# 32u4_Simple_Breakout.net
KiCad netlist of a schematic drawn in EAGLE
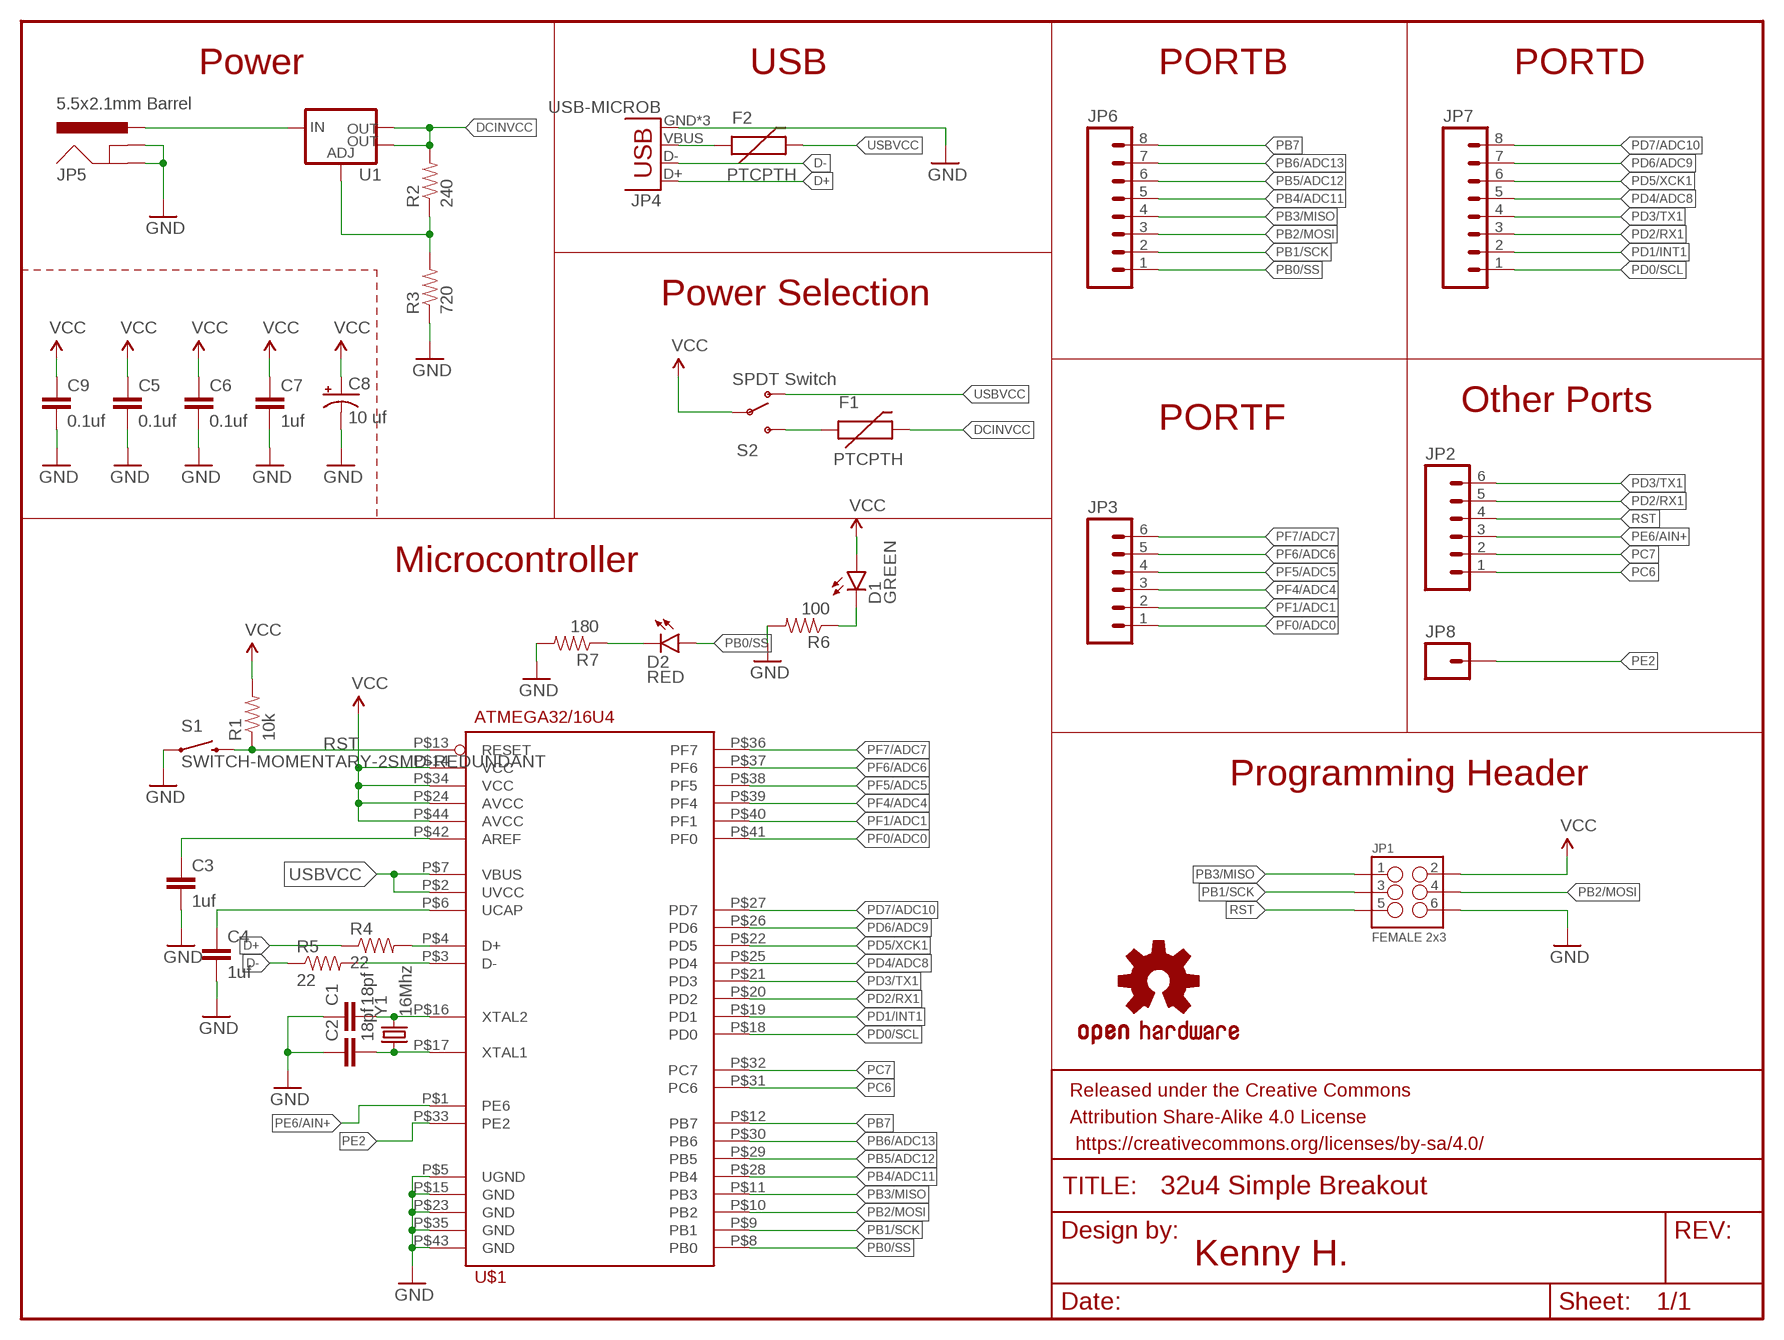
[diagram p0: schematic, sheet 1]

(export (version "E")
  (design (tool "Eeschema 10.0.6"))
  (components
    (comp (ref "C1")
      (value "18pf")
      (footprint "eagle-import:0603-CAP")
      (libsource (lib "eagle-import") (part "CAP0603-CAP"))
    )
    (comp (ref "C2")
      (value "18pf")
      (footprint "eagle-import:0603-CAP")
      (libsource (lib "eagle-import") (part "CAP0603-CAP"))
    )
    (comp (ref "C3")
      (value "1uf")
      (footprint "eagle-import:0603-CAP")
      (libsource (lib "eagle-import") (part "CAP0603-CAP"))
    )
    (comp (ref "C4")
      (value "1uf")
      (footprint "eagle-import:0603-CAP")
      (libsource (lib "eagle-import") (part "CAP0603-CAP"))
    )
    (comp (ref "C5")
      (value "0.1uf")
      (footprint "eagle-import:0603-CAP")
      (libsource (lib "eagle-import") (part "CAP0603-CAP"))
    )
    (comp (ref "C6")
      (value "0.1uf")
      (footprint "eagle-import:0603-CAP")
      (libsource (lib "eagle-import") (part "CAP0603-CAP"))
    )
    (comp (ref "C7")
      (value "1uf")
      (footprint "eagle-import:0603-CAP")
      (libsource (lib "eagle-import") (part "CAP0603-CAP"))
    )
    (comp (ref "C8")
      (value "10 uf")
      (footprint "eagle-import:CPOL-RADIAL-10UF-25V")
      (libsource (lib "eagle-import") (part "CAP_POLPTH2"))
    )
    (comp (ref "C9")
      (value "0.1uf")
      (footprint "eagle-import:0603-CAP")
      (libsource (lib "eagle-import") (part "CAP0603-CAP"))
    )
    (comp (ref "D1")
      (value "GREEN")
      (footprint "eagle-import:LED-1206")
      (libsource (lib "eagle-import") (part "LED-GREEN1206"))
    )
    (comp (ref "D2")
      (value "RED")
      (footprint "eagle-import:LED-1206")
      (libsource (lib "eagle-import") (part "LED-RED1206"))
    )
    (comp (ref "F1")
      (value "PTCPTH")
      (footprint "eagle-import:PTC")
      (libsource (lib "eagle-import") (part "PTCPTH"))
    )
    (comp (ref "F2")
      (value "PTCPTH")
      (footprint "eagle-import:PTC")
      (libsource (lib "eagle-import") (part "PTCPTH"))
    )
    (comp (ref "FRAME1")
      (value "FRAME-LETTER")
      (footprint "eagle-import:CREATIVE_COMMONS")
      (libsource (lib "eagle-import") (part "FRAME-LETTER"))
    )
    (comp (ref "JP1")
      (value "FEMALE 2x3")
      (footprint "eagle-import:2X3")
      (libsource (lib "eagle-import") (part "M03X2FEMALE"))
    )
    (comp (ref "JP2")
      (value "M06FEMALE_LOCK")
      (footprint "eagle-import:1X06_FEMALE_LOCK.010")
      (libsource (lib "eagle-import") (part "M06FEMALE_LOCK"))
    )
    (comp (ref "JP3")
      (value "M06FEMALE_LOCK")
      (footprint "eagle-import:1X06_FEMALE_LOCK.010")
      (libsource (lib "eagle-import") (part "M06FEMALE_LOCK"))
    )
    (comp (ref "JP4")
      (value "USB-MICROB")
      (footprint "eagle-import:USB-MICROB")
      (libsource (lib "eagle-import") (part "USB-MICROB"))
    )
    (comp (ref "JP5")
      (value "5.5x2.1mm Barrel")
      (footprint "eagle-import:POWER_JACK_SMD")
      (libsource (lib "eagle-import") (part "POWER_JACKSMD"))
    )
    (comp (ref "JP6")
      (value "M08FEMALE_LOCK")
      (footprint "eagle-import:1X08_FEMALE_LOCK")
      (libsource (lib "eagle-import") (part "M08FEMALE_LOCK"))
    )
    (comp (ref "JP7")
      (value "M08FEMALE_LOCK")
      (footprint "eagle-import:1X08_FEMALE_LOCK")
      (libsource (lib "eagle-import") (part "M08FEMALE_LOCK"))
    )
    (comp (ref "JP8")
      (value "M01PTH")
      (footprint "eagle-import:1X01")
      (libsource (lib "eagle-import") (part "M01PTH"))
    )
    (comp (ref "LOGO1")
      (value "OSHW-LOGOM")
      (footprint "eagle-import:OSHW-LOGO-M")
      (libsource (lib "eagle-import") (part "OSHW-LOGOM"))
    )
    (comp (ref "R1")
      (value "10k")
      (footprint "eagle-import:0603-RES")
      (libsource (lib "eagle-import") (part "RESISTOR0603-RES"))
    )
    (comp (ref "R2")
      (value "240")
      (footprint "eagle-import:0603-RES")
      (libsource (lib "eagle-import") (part "RESISTOR0603-RES"))
    )
    (comp (ref "R3")
      (value "720")
      (footprint "eagle-import:0603-RES")
      (libsource (lib "eagle-import") (part "RESISTOR0603-RES"))
    )
    (comp (ref "R4")
      (value "22")
      (footprint "eagle-import:0603-RES")
      (libsource (lib "eagle-import") (part "SparkFun-Resistors_RESISTOR0603-RES"))
    )
    (comp (ref "R5")
      (value "22")
      (footprint "eagle-import:0603-RES")
      (libsource (lib "eagle-import") (part "SparkFun-Resistors_RESISTOR0603-RES"))
    )
    (comp (ref "R6")
      (value "100")
      (footprint "eagle-import:1206")
      (libsource (lib "eagle-import") (part "SparkFun-Resistors_RESISTOR1206"))
    )
    (comp (ref "R7")
      (value "180")
      (footprint "eagle-import:1206")
      (libsource (lib "eagle-import") (part "SparkFun-Resistors_RESISTOR1206"))
    )
    (comp (ref "S1")
      (value "SWITCH-MOMENTARY-2SMD-REDUNDANT")
      (footprint "eagle-import:TACTILE-SWITCH-SMD")
      (libsource (lib "eagle-import") (part "SWITCH-MOMENTARY-2SMD-REDUNDANT"))
    )
    (comp (ref "S2")
      (value "SPDT Switch")
      (footprint "eagle-import:SWITCH-SPST-SMD-A")
      (libsource (lib "eagle-import") (part "SWITCH-SPDT-SMD-A"))
    )
    (comp (ref "U$1")
      (value "ATMEGA32/16U4")
      (footprint "eagle-import:TQFP_44_0.8MM")
      (libsource (lib "eagle-import") (part "ATMEGA32/16U4"))
    )
    (comp (ref "U1")
      (value "V_REG_LM1117SOT223")
      (footprint "eagle-import:SOT223")
      (libsource (lib "eagle-import") (part "V_REG_LM1117SOT223"))
    )
    (comp (ref "Y1")
      (value "16Mhz")
      (footprint "eagle-import:CRYSTAL-SMD-5X3")
      (libsource (lib "eagle-import") (part "CRYSTAL5X3"))
    )
  )
  (nets
    (net (code "1") (name "D+") (class "Default")
      (node (ref "JP4") (pin "D+") (pinfunction "D+_D+") (pintype "bidirectional"))
      (node (ref "R4") (pin "1") (pinfunction "1_1") (pintype "passive"))
    )
    (net (code "2") (name "D-") (class "Default")
      (node (ref "JP4") (pin "D-") (pinfunction "D-_D-") (pintype "bidirectional"))
      (node (ref "R5") (pin "1") (pinfunction "1_1") (pintype "passive"))
    )
    (net (code "3") (name "DCINVCC") (class "Default")
      (node (ref "F1") (pin "P$2") (pinfunction "2_P$2") (pintype "bidirectional"))
      (node (ref "R2") (pin "2") (pinfunction "2_2") (pintype "passive"))
      (node (ref "U1") (pin "2") (pinfunction "OUT_2") (pintype "output"))
      (node (ref "U1") (pin "4") (pinfunction "OUT_4") (pintype "output"))
    )
    (net (code "4") (name "GND") (class "Default")
      (node (ref "C1") (pin "1") (pinfunction "1_1") (pintype "passive"))
      (node (ref "C2") (pin "1") (pinfunction "1_1") (pintype "passive"))
      (node (ref "C3") (pin "2") (pinfunction "2_2") (pintype "passive"))
      (node (ref "C4") (pin "2") (pinfunction "2_2") (pintype "passive"))
      (node (ref "C5") (pin "2") (pinfunction "2_2") (pintype "passive"))
      (node (ref "C6") (pin "2") (pinfunction "2_2") (pintype "passive"))
      (node (ref "C7") (pin "2") (pinfunction "2_2") (pintype "passive"))
      (node (ref "C8") (pin "2") (pinfunction "-_2") (pintype "passive"))
      (node (ref "C9") (pin "2") (pinfunction "2_2") (pintype "passive"))
      (node (ref "JP1") (pin "6") (pinfunction "6_6") (pintype "bidirectional"))
      (node (ref "JP4") (pin "GND") (pinfunction "GND_GND") (pintype "bidirectional"))
      (node (ref "JP4") (pin "MT1") (pinfunction "GND_MT1") (pintype "bidirectional"))
      (node (ref "JP4") (pin "MT2") (pinfunction "GND_MT2") (pintype "bidirectional"))
      (node (ref "JP5") (pin "GND") (pinfunction "GNDBREAK_GND") (pintype "bidirectional"))
      (node (ref "JP5") (pin "P$4") (pinfunction "GND_P$4") (pintype "bidirectional"))
      (node (ref "R3") (pin "1") (pinfunction "1_1") (pintype "passive"))
      (node (ref "R6") (pin "2") (pinfunction "2_2") (pintype "passive"))
      (node (ref "R7") (pin "2") (pinfunction "2_2") (pintype "passive"))
      (node (ref "S1") (pin "1") (pinfunction "1_1") (pintype "passive"))
      (node (ref "S1") (pin "2") (pinfunction "1_2") (pintype "passive"))
      (node (ref "U$1") (pin "P$15") (pinfunction "GND_P$15") (pintype "power_in"))
      (node (ref "U$1") (pin "P$23") (pinfunction "GND_P$23") (pintype "power_in"))
      (node (ref "U$1") (pin "P$35") (pinfunction "GND_P$35") (pintype "power_in"))
      (node (ref "U$1") (pin "P$43") (pinfunction "GND_P$43") (pintype "power_in"))
      (node (ref "U$1") (pin "P$5") (pinfunction "UGND_P$5") (pintype "power_in"))
    )
    (net (code "5") (name "Net-(D1-PadC)") (class "Default")
      (node (ref "D1") (pin "C") (pinfunction "C_C") (pintype "passive"))
      (node (ref "R6") (pin "1") (pinfunction "1_1") (pintype "passive"))
    )
    (net (code "6") (name "Net-(D2-PadC)") (class "Default")
      (node (ref "D2") (pin "C") (pinfunction "C_C") (pintype "passive"))
      (node (ref "R7") (pin "1") (pinfunction "1_1") (pintype "passive"))
    )
    (net (code "7") (name "Net-(F1-1)") (class "Default")
      (node (ref "F1") (pin "P$1") (pinfunction "1_P$1") (pintype "bidirectional"))
      (node (ref "S2") (pin "3") (pinfunction "S_3") (pintype "passive"))
    )
    (net (code "8") (name "Net-(F2-1)") (class "Default")
      (node (ref "F2") (pin "P$1") (pinfunction "1_P$1") (pintype "bidirectional"))
      (node (ref "JP4") (pin "VBUS") (pinfunction "VBUS_VBUS") (pintype "bidirectional"))
    )
    (net (code "9") (name "Net-(JP5-PWR)") (class "Default")
      (node (ref "JP5") (pin "VIN0") (pinfunction "PWR_VIN0") (pintype "bidirectional"))
      (node (ref "U1") (pin "3") (pinfunction "IN_3") (pintype "input"))
    )
    (net (code "10") (name "Net-(U$1-AREF)") (class "Default")
      (node (ref "C3") (pin "1") (pinfunction "1_1") (pintype "passive"))
      (node (ref "U$1") (pin "P$42") (pinfunction "AREF_P$42") (pintype "power_in"))
    )
    (net (code "11") (name "Net-(U$1-D+)") (class "Default")
      (node (ref "R4") (pin "2") (pinfunction "2_2") (pintype "passive"))
      (node (ref "U$1") (pin "P$4") (pinfunction "D+_P$4") (pintype "bidirectional"))
    )
    (net (code "12") (name "Net-(U$1-D-)") (class "Default")
      (node (ref "R5") (pin "2") (pinfunction "2_2") (pintype "passive"))
      (node (ref "U$1") (pin "P$3") (pinfunction "D-_P$3") (pintype "bidirectional"))
    )
    (net (code "13") (name "Net-(U$1-UCAP)") (class "Default")
      (node (ref "C4") (pin "1") (pinfunction "1_1") (pintype "passive"))
      (node (ref "U$1") (pin "P$6") (pinfunction "UCAP_P$6") (pintype "power_in"))
    )
    (net (code "14") (name "Net-(U$1-XTAL1)") (class "Default")
      (node (ref "C2") (pin "2") (pinfunction "2_2") (pintype "passive"))
      (node (ref "U$1") (pin "P$17") (pinfunction "XTAL1_P$17") (pintype "input"))
      (node (ref "Y1") (pin "1") (pinfunction "1_1") (pintype "passive"))
    )
    (net (code "15") (name "Net-(U$1-XTAL2)") (class "Default")
      (node (ref "C1") (pin "2") (pinfunction "2_2") (pintype "passive"))
      (node (ref "U$1") (pin "P$16") (pinfunction "XTAL2_P$16") (pintype "input"))
      (node (ref "Y1") (pin "3") (pinfunction "2_3") (pintype "passive"))
    )
    (net (code "16") (name "Net-(U1-ADJ)") (class "Default")
      (node (ref "R2") (pin "1") (pinfunction "1_1") (pintype "passive"))
      (node (ref "R3") (pin "2") (pinfunction "2_2") (pintype "passive"))
      (node (ref "U1") (pin "1") (pinfunction "ADJ_1") (pintype "input"))
    )
    (net (code "17") (name "PB0{slash}SS") (class "Default")
      (node (ref "D2") (pin "A") (pinfunction "A_A") (pintype "passive"))
      (node (ref "JP6") (pin "1") (pinfunction "1_1") (pintype "passive"))
      (node (ref "U$1") (pin "P$8") (pinfunction "PB0_P$8") (pintype "bidirectional"))
    )
    (net (code "18") (name "PB1{slash}SCK") (class "Default")
      (node (ref "JP1") (pin "3") (pinfunction "3_3") (pintype "bidirectional"))
      (node (ref "JP6") (pin "2") (pinfunction "2_2") (pintype "passive"))
      (node (ref "U$1") (pin "P$9") (pinfunction "PB1_P$9") (pintype "bidirectional"))
    )
    (net (code "19") (name "PB2{slash}MOSI") (class "Default")
      (node (ref "JP1") (pin "4") (pinfunction "4_4") (pintype "bidirectional"))
      (node (ref "JP6") (pin "3") (pinfunction "3_3") (pintype "passive"))
      (node (ref "U$1") (pin "P$10") (pinfunction "PB2_P$10") (pintype "bidirectional"))
    )
    (net (code "20") (name "PB3{slash}MISO") (class "Default")
      (node (ref "JP1") (pin "1") (pinfunction "1_1") (pintype "bidirectional"))
      (node (ref "JP6") (pin "4") (pinfunction "4_4") (pintype "passive"))
      (node (ref "U$1") (pin "P$11") (pinfunction "PB3_P$11") (pintype "bidirectional"))
    )
    (net (code "21") (name "PB4{slash}ADC11") (class "Default")
      (node (ref "JP6") (pin "5") (pinfunction "5_5") (pintype "passive"))
      (node (ref "U$1") (pin "P$28") (pinfunction "PB4_P$28") (pintype "bidirectional"))
    )
    (net (code "22") (name "PB5{slash}ADC12") (class "Default")
      (node (ref "JP6") (pin "6") (pinfunction "6_6") (pintype "passive"))
      (node (ref "U$1") (pin "P$29") (pinfunction "PB5_P$29") (pintype "bidirectional"))
    )
    (net (code "23") (name "PB6{slash}ADC13") (class "Default")
      (node (ref "JP6") (pin "7") (pinfunction "7_7") (pintype "passive"))
      (node (ref "U$1") (pin "P$30") (pinfunction "PB6_P$30") (pintype "bidirectional"))
    )
    (net (code "24") (name "PB7") (class "Default")
      (node (ref "JP6") (pin "8") (pinfunction "8_8") (pintype "passive"))
      (node (ref "U$1") (pin "P$12") (pinfunction "PB7_P$12") (pintype "bidirectional"))
    )
    (net (code "25") (name "PC6") (class "Default")
      (node (ref "JP2") (pin "1") (pinfunction "1_1") (pintype "passive"))
      (node (ref "U$1") (pin "P$31") (pinfunction "PC6_P$31") (pintype "bidirectional"))
    )
    (net (code "26") (name "PC7") (class "Default")
      (node (ref "JP2") (pin "2") (pinfunction "2_2") (pintype "passive"))
      (node (ref "U$1") (pin "P$32") (pinfunction "PC7_P$32") (pintype "bidirectional"))
    )
    (net (code "27") (name "PD0{slash}SCL") (class "Default")
      (node (ref "JP7") (pin "1") (pinfunction "1_1") (pintype "passive"))
      (node (ref "U$1") (pin "P$18") (pinfunction "PD0_P$18") (pintype "bidirectional"))
    )
    (net (code "28") (name "PD1{slash}INT1") (class "Default")
      (node (ref "JP7") (pin "2") (pinfunction "2_2") (pintype "passive"))
      (node (ref "U$1") (pin "P$19") (pinfunction "PD1_P$19") (pintype "bidirectional"))
    )
    (net (code "29") (name "PD2{slash}RX1") (class "Default")
      (node (ref "JP2") (pin "5") (pinfunction "5_5") (pintype "passive"))
      (node (ref "JP7") (pin "3") (pinfunction "3_3") (pintype "passive"))
      (node (ref "U$1") (pin "P$20") (pinfunction "PD2_P$20") (pintype "bidirectional"))
    )
    (net (code "30") (name "PD3{slash}TX1") (class "Default")
      (node (ref "JP2") (pin "6") (pinfunction "6_6") (pintype "passive"))
      (node (ref "JP7") (pin "4") (pinfunction "4_4") (pintype "passive"))
      (node (ref "U$1") (pin "P$21") (pinfunction "PD3_P$21") (pintype "bidirectional"))
    )
    (net (code "31") (name "PD4{slash}ADC8") (class "Default")
      (node (ref "JP7") (pin "5") (pinfunction "5_5") (pintype "passive"))
      (node (ref "U$1") (pin "P$25") (pinfunction "PD4_P$25") (pintype "bidirectional"))
    )
    (net (code "32") (name "PD5{slash}XCK1") (class "Default")
      (node (ref "JP7") (pin "6") (pinfunction "6_6") (pintype "passive"))
      (node (ref "U$1") (pin "P$22") (pinfunction "PD5_P$22") (pintype "bidirectional"))
    )
    (net (code "33") (name "PD6{slash}ADC9") (class "Default")
      (node (ref "JP7") (pin "7") (pinfunction "7_7") (pintype "passive"))
      (node (ref "U$1") (pin "P$26") (pinfunction "PD6_P$26") (pintype "bidirectional"))
    )
    (net (code "34") (name "PD7{slash}ADC10") (class "Default")
      (node (ref "JP7") (pin "8") (pinfunction "8_8") (pintype "passive"))
      (node (ref "U$1") (pin "P$27") (pinfunction "PD7_P$27") (pintype "bidirectional"))
    )
    (net (code "35") (name "PE2") (class "Default")
      (node (ref "JP8") (pin "1") (pinfunction "1_1") (pintype "passive"))
      (node (ref "U$1") (pin "P$33") (pinfunction "PE2_P$33") (pintype "bidirectional"))
    )
    (net (code "36") (name "PE6{slash}AIN+") (class "Default")
      (node (ref "JP2") (pin "3") (pinfunction "3_3") (pintype "passive"))
      (node (ref "U$1") (pin "P$1") (pinfunction "PE6_P$1") (pintype "bidirectional"))
    )
    (net (code "37") (name "PF0{slash}ADC0") (class "Default")
      (node (ref "JP3") (pin "1") (pinfunction "1_1") (pintype "passive"))
      (node (ref "U$1") (pin "P$41") (pinfunction "PF0_P$41") (pintype "bidirectional"))
    )
    (net (code "38") (name "PF1{slash}ADC1") (class "Default")
      (node (ref "JP3") (pin "2") (pinfunction "2_2") (pintype "passive"))
      (node (ref "U$1") (pin "P$40") (pinfunction "PF1_P$40") (pintype "bidirectional"))
    )
    (net (code "39") (name "PF4{slash}ADC4") (class "Default")
      (node (ref "JP3") (pin "3") (pinfunction "3_3") (pintype "passive"))
      (node (ref "U$1") (pin "P$39") (pinfunction "PF4_P$39") (pintype "bidirectional"))
    )
    (net (code "40") (name "PF5{slash}ADC5") (class "Default")
      (node (ref "JP3") (pin "4") (pinfunction "4_4") (pintype "passive"))
      (node (ref "U$1") (pin "P$38") (pinfunction "PF5_P$38") (pintype "bidirectional"))
    )
    (net (code "41") (name "PF6{slash}ADC6") (class "Default")
      (node (ref "JP3") (pin "5") (pinfunction "5_5") (pintype "passive"))
      (node (ref "U$1") (pin "P$37") (pinfunction "PF6_P$37") (pintype "bidirectional"))
    )
    (net (code "42") (name "PF7{slash}ADC7") (class "Default")
      (node (ref "JP3") (pin "6") (pinfunction "6_6") (pintype "passive"))
      (node (ref "U$1") (pin "P$36") (pinfunction "PF7_P$36") (pintype "bidirectional"))
    )
    (net (code "43") (name "RST") (class "Default")
      (node (ref "JP1") (pin "5") (pinfunction "5_5") (pintype "bidirectional"))
      (node (ref "JP2") (pin "4") (pinfunction "4_4") (pintype "passive"))
      (node (ref "R1") (pin "1") (pinfunction "1_1") (pintype "passive"))
      (node (ref "S1") (pin "3") (pinfunction "2_3") (pintype "passive"))
      (node (ref "S1") (pin "4") (pinfunction "2_4") (pintype "passive"))
      (node (ref "U$1") (pin "P$13") (pinfunction "RESET_P$13") (pintype "input"))
    )
    (net (code "44") (name "USBVCC") (class "Default")
      (node (ref "F2") (pin "P$2") (pinfunction "2_P$2") (pintype "bidirectional"))
      (node (ref "S2") (pin "1") (pinfunction "O_1") (pintype "passive"))
      (node (ref "U$1") (pin "P$2") (pinfunction "UVCC_P$2") (pintype "power_in"))
      (node (ref "U$1") (pin "P$7") (pinfunction "VBUS_P$7") (pintype "power_in"))
    )
    (net (code "45") (name "VCC") (class "Default")
      (node (ref "C5") (pin "1") (pinfunction "1_1") (pintype "passive"))
      (node (ref "C6") (pin "1") (pinfunction "1_1") (pintype "passive"))
      (node (ref "C7") (pin "1") (pinfunction "1_1") (pintype "passive"))
      (node (ref "C8") (pin "1") (pinfunction "+_1") (pintype "passive"))
      (node (ref "C9") (pin "1") (pinfunction "1_1") (pintype "passive"))
      (node (ref "D1") (pin "A") (pinfunction "A_A") (pintype "passive"))
      (node (ref "JP1") (pin "2") (pinfunction "2_2") (pintype "bidirectional"))
      (node (ref "R1") (pin "2") (pinfunction "2_2") (pintype "passive"))
      (node (ref "S2") (pin "2") (pinfunction "P_2") (pintype "passive"))
      (node (ref "U$1") (pin "P$14") (pinfunction "VCC_P$14") (pintype "power_in"))
      (node (ref "U$1") (pin "P$24") (pinfunction "AVCC_P$24") (pintype "power_in"))
      (node (ref "U$1") (pin "P$34") (pinfunction "VCC_P$34") (pintype "power_in"))
      (node (ref "U$1") (pin "P$44") (pinfunction "AVCC_P$44") (pintype "power_in"))
    )
  )
)
